# transmitter.net
KiCad netlist of a schematic drawn in EAGLE
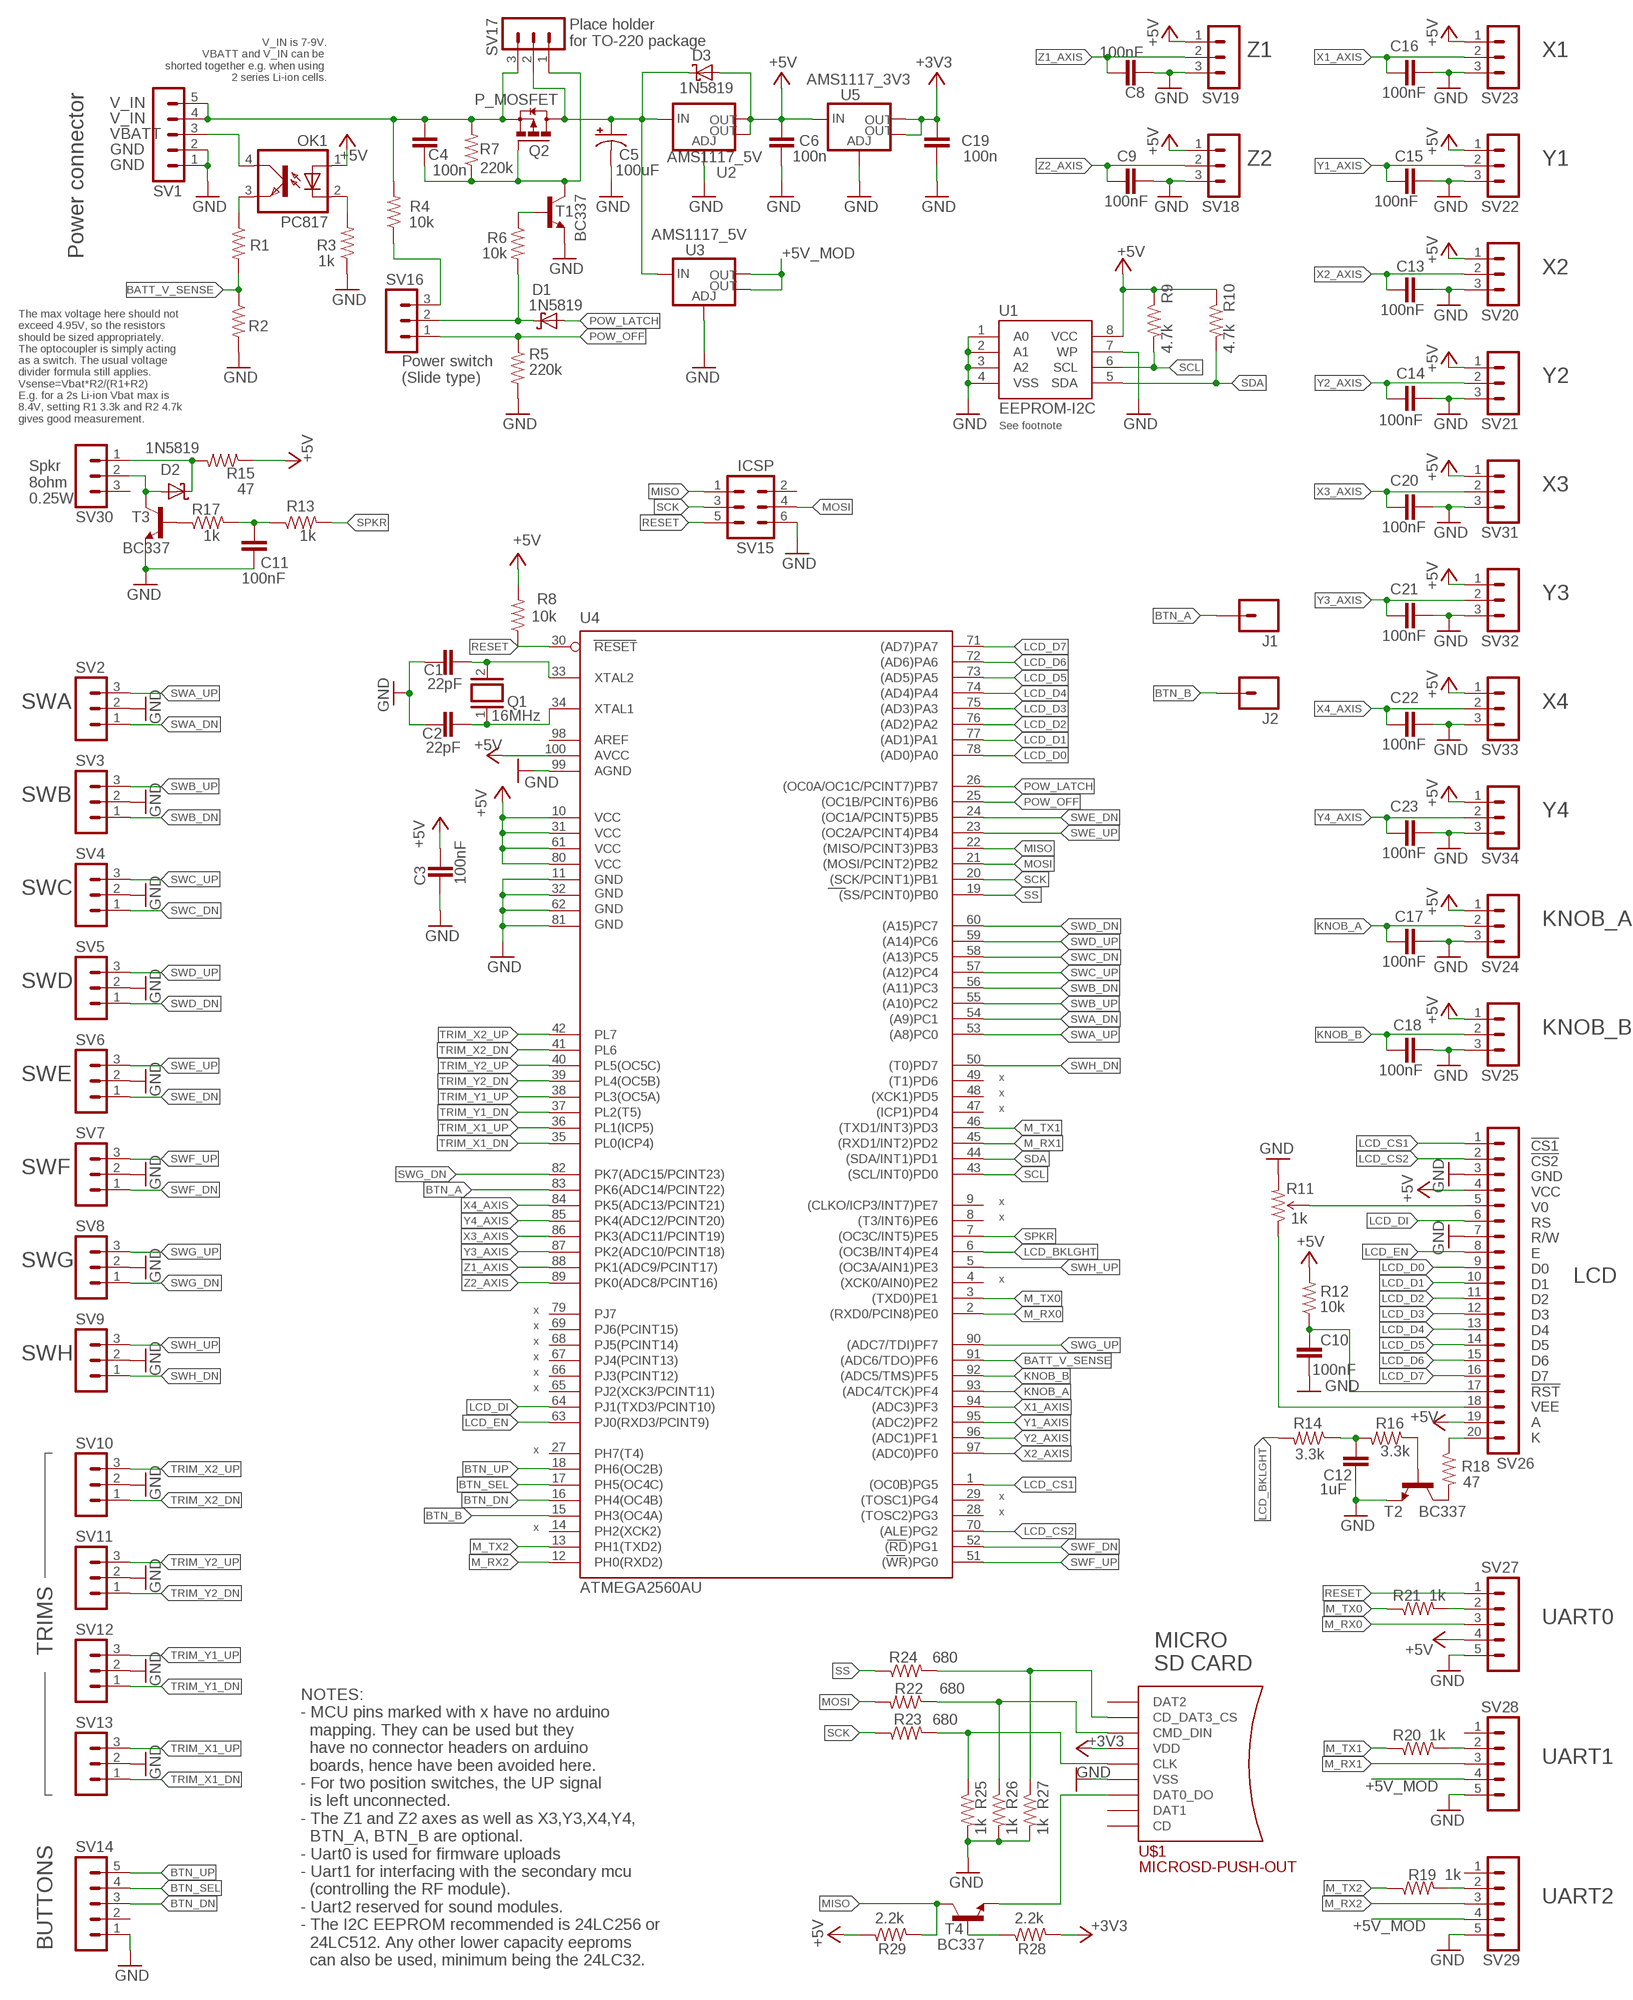
[diagram p0: schematic, sheet 1]

(export (version "E")
  (design (tool "Eeschema 10.0.6"))
  (components
    (comp (ref "C1")
      (value "22pF")
      (footprint "eagle-import:C050-024X044")
      (libsource (lib "eagle-import") (part "C-EU050-024X044"))
    )
    (comp (ref "C2")
      (value "22pF")
      (footprint "eagle-import:C050-024X044")
      (libsource (lib "eagle-import") (part "C-EU050-024X044"))
    )
    (comp (ref "C3")
      (value "100nF")
      (footprint "eagle-import:C050-024X044")
      (libsource (lib "eagle-import") (part "C-EU050-024X044"))
    )
    (comp (ref "C4")
      (value "100n")
      (footprint "eagle-import:C050-024X044")
      (libsource (lib "eagle-import") (part "C-EU050-024X044"))
    )
    (comp (ref "C5")
      (value "100uF")
      (footprint "eagle-import:E2,5-6E")
      (libsource (lib "eagle-import") (part "CPOL-USE2,5-6E"))
    )
    (comp (ref "C6")
      (value "100n")
      (footprint "eagle-import:C050-024X044")
      (libsource (lib "eagle-import") (part "C-EU050-024X044"))
    )
    (comp (ref "C8")
      (value "100nF")
      (footprint "eagle-import:C050-024X044")
      (libsource (lib "eagle-import") (part "C-EU050-024X044"))
    )
    (comp (ref "C9")
      (value "100nF")
      (footprint "eagle-import:C050-024X044")
      (libsource (lib "eagle-import") (part "C-EU050-024X044"))
    )
    (comp (ref "C10")
      (value "100nF")
      (footprint "eagle-import:C050-024X044")
      (libsource (lib "eagle-import") (part "C-EU050-024X044"))
    )
    (comp (ref "C11")
      (value "100nF")
      (footprint "eagle-import:C050-024X044")
      (libsource (lib "eagle-import") (part "C-EU050-024X044"))
    )
    (comp (ref "C12")
      (value "1uF")
      (footprint "eagle-import:C050-024X044")
      (libsource (lib "eagle-import") (part "C-EU050-024X044"))
    )
    (comp (ref "C13")
      (value "100nF")
      (footprint "eagle-import:C050-024X044")
      (libsource (lib "eagle-import") (part "C-EU050-024X044"))
    )
    (comp (ref "C14")
      (value "100nF")
      (footprint "eagle-import:C050-024X044")
      (libsource (lib "eagle-import") (part "C-EU050-024X044"))
    )
    (comp (ref "C15")
      (value "100nF")
      (footprint "eagle-import:C050-024X044")
      (libsource (lib "eagle-import") (part "C-EU050-024X044"))
    )
    (comp (ref "C16")
      (value "100nF")
      (footprint "eagle-import:C050-024X044")
      (libsource (lib "eagle-import") (part "C-EU050-024X044"))
    )
    (comp (ref "C17")
      (value "100nF")
      (footprint "eagle-import:C050-024X044")
      (libsource (lib "eagle-import") (part "C-EU050-024X044"))
    )
    (comp (ref "C18")
      (value "100nF")
      (footprint "eagle-import:C050-024X044")
      (libsource (lib "eagle-import") (part "C-EU050-024X044"))
    )
    (comp (ref "C19")
      (value "100n")
      (footprint "eagle-import:C050-024X044")
      (libsource (lib "eagle-import") (part "C-EU050-024X044"))
    )
    (comp (ref "C20")
      (value "100nF")
      (footprint "eagle-import:C050-024X044")
      (libsource (lib "eagle-import") (part "C-EU050-024X044"))
    )
    (comp (ref "C21")
      (value "100nF")
      (footprint "eagle-import:C050-024X044")
      (libsource (lib "eagle-import") (part "C-EU050-024X044"))
    )
    (comp (ref "C22")
      (value "100nF")
      (footprint "eagle-import:C050-024X044")
      (libsource (lib "eagle-import") (part "C-EU050-024X044"))
    )
    (comp (ref "C23")
      (value "100nF")
      (footprint "eagle-import:C050-024X044")
      (libsource (lib "eagle-import") (part "C-EU050-024X044"))
    )
    (comp (ref "D1")
      (value "1N5819")
      (footprint "eagle-import:DO41-7.6")
      (libsource (lib "eagle-import") (part "1N5817-B"))
    )
    (comp (ref "D2")
      (value "1N5819")
      (footprint "eagle-import:DO41-7.6")
      (libsource (lib "eagle-import") (part "1N5817-B"))
    )
    (comp (ref "D3")
      (value "1N5819")
      (footprint "eagle-import:DO41-7.6")
      (libsource (lib "eagle-import") (part "1N5817-B"))
    )
    (comp (ref "J1")
      (value "M01PTH_LONGPAD")
      (footprint "eagle-import:1X01_LONGPAD")
      (libsource (lib "eagle-import") (part "M01PTH_LONGPAD"))
    )
    (comp (ref "J2")
      (value "M01PTH_LONGPAD")
      (footprint "eagle-import:1X01_LONGPAD")
      (libsource (lib "eagle-import") (part "M01PTH_LONGPAD"))
    )
    (comp (ref "OK1")
      (value "PC817")
      (footprint "eagle-import:DIL04")
      (fields (field (name "MPN") "PC817X4J000F"))
      (libsource (lib "eagle-import") (part "PC817"))
    )
    (comp (ref "Q1")
      (value "16MHz")
      (footprint "eagle-import:QS")
      (libsource (lib "eagle-import") (part "XTAL/S"))
    )
    (comp (ref "Q2")
      (value "P_MOSFET")
      (footprint "eagle-import:SUPER-SOT3")
      (libsource (lib "eagle-import") (part "FDN360P"))
    )
    (comp (ref "R1")
      (value "1k")
      (footprint "eagle-import:0204_5")
      (libsource (lib "eagle-import") (part "R-US_0204/5"))
    )
    (comp (ref "R2")
      (value "1k")
      (footprint "eagle-import:0204_5")
      (libsource (lib "eagle-import") (part "R-US_0204/5"))
    )
    (comp (ref "R3")
      (value "1k")
      (footprint "eagle-import:0204_5")
      (libsource (lib "eagle-import") (part "R-US_0204/5"))
    )
    (comp (ref "R4")
      (value "10k")
      (footprint "eagle-import:0204_5")
      (libsource (lib "eagle-import") (part "R-US_0204/5"))
    )
    (comp (ref "R5")
      (value "220k")
      (footprint "eagle-import:0204_5")
      (libsource (lib "eagle-import") (part "R-US_0204/5"))
    )
    (comp (ref "R6")
      (value "10k")
      (footprint "eagle-import:0204_5")
      (libsource (lib "eagle-import") (part "R-US_0204/5"))
    )
    (comp (ref "R7")
      (value "220k")
      (footprint "eagle-import:0204_5")
      (libsource (lib "eagle-import") (part "R-US_0204/5"))
    )
    (comp (ref "R8")
      (value "10k")
      (footprint "eagle-import:0204_5")
      (libsource (lib "eagle-import") (part "R-US_0204/5"))
    )
    (comp (ref "R9")
      (value "4.7k")
      (footprint "eagle-import:0204_5")
      (libsource (lib "eagle-import") (part "R-US_0204/5"))
    )
    (comp (ref "R10")
      (value "4.7k")
      (footprint "eagle-import:0204_5")
      (libsource (lib "eagle-import") (part "R-US_0204/5"))
    )
    (comp (ref "R11")
      (value "1k")
      (footprint "eagle-import:TRIM_POT_PTH")
      (libsource (lib "eagle-import") (part "TRIMPOTPTH"))
    )
    (comp (ref "R12")
      (value "10k")
      (footprint "eagle-import:0204_5")
      (libsource (lib "eagle-import") (part "resistor_R-US_0204/5"))
    )
    (comp (ref "R13")
      (value "1k")
      (footprint "eagle-import:0204_5")
      (libsource (lib "eagle-import") (part "R-US_0204/5"))
    )
    (comp (ref "R14")
      (value "3.3k")
      (footprint "eagle-import:0204_5")
      (libsource (lib "eagle-import") (part "R-US_0204/5"))
    )
    (comp (ref "R15")
      (value "47")
      (footprint "eagle-import:0204_5")
      (libsource (lib "eagle-import") (part "R-US_0204/5"))
    )
    (comp (ref "R16")
      (value "3.3k")
      (footprint "eagle-import:0204_5")
      (libsource (lib "eagle-import") (part "R-US_0204/5"))
    )
    (comp (ref "R17")
      (value "1k")
      (footprint "eagle-import:0204_5")
      (libsource (lib "eagle-import") (part "R-US_0204/5"))
    )
    (comp (ref "R18")
      (value "47")
      (footprint "eagle-import:0204_5")
      (libsource (lib "eagle-import") (part "R-US_0204/5"))
    )
    (comp (ref "R19")
      (value "1k")
      (footprint "eagle-import:0204_5")
      (libsource (lib "eagle-import") (part "R-US_0204/5"))
    )
    (comp (ref "R20")
      (value "1k")
      (footprint "eagle-import:0204_5")
      (libsource (lib "eagle-import") (part "R-US_0204/5"))
    )
    (comp (ref "R21")
      (value "1k")
      (footprint "eagle-import:0204_5")
      (libsource (lib "eagle-import") (part "R-US_0204/5"))
    )
    (comp (ref "R22")
      (value "680")
      (footprint "eagle-import:0204_5")
      (libsource (lib "eagle-import") (part "R-US_0204/5"))
    )
    (comp (ref "R23")
      (value "680")
      (footprint "eagle-import:0204_5")
      (libsource (lib "eagle-import") (part "R-US_0204/5"))
    )
    (comp (ref "R24")
      (value "680")
      (footprint "eagle-import:0204_5")
      (libsource (lib "eagle-import") (part "R-US_0204/5"))
    )
    (comp (ref "R25")
      (value "1k")
      (footprint "eagle-import:0204_5")
      (libsource (lib "eagle-import") (part "R-US_0204/5"))
    )
    (comp (ref "R26")
      (value "1k")
      (footprint "eagle-import:0204_5")
      (libsource (lib "eagle-import") (part "R-US_0204/5"))
    )
    (comp (ref "R27")
      (value "1k")
      (footprint "eagle-import:0204_5")
      (libsource (lib "eagle-import") (part "R-US_0204/5"))
    )
    (comp (ref "R28")
      (value "2.2k")
      (footprint "eagle-import:0204_5")
      (libsource (lib "eagle-import") (part "R-US_0204/5"))
    )
    (comp (ref "R29")
      (value "2.2k")
      (footprint "eagle-import:0204_5")
      (libsource (lib "eagle-import") (part "R-US_0204/5"))
    )
    (comp (ref "SV1")
      (value "MA05-1")
      (footprint "eagle-import:MA05-1")
      (libsource (lib "eagle-import") (part "MA05-1"))
    )
    (comp (ref "SV2")
      (value "MA03-1")
      (footprint "eagle-import:MA03-1")
      (libsource (lib "eagle-import") (part "MA03-1"))
    )
    (comp (ref "SV3")
      (value "MA03-1")
      (footprint "eagle-import:MA03-1")
      (libsource (lib "eagle-import") (part "MA03-1"))
    )
    (comp (ref "SV4")
      (value "MA03-1")
      (footprint "eagle-import:MA03-1")
      (libsource (lib "eagle-import") (part "MA03-1"))
    )
    (comp (ref "SV5")
      (value "MA03-1")
      (footprint "eagle-import:MA03-1")
      (libsource (lib "eagle-import") (part "MA03-1"))
    )
    (comp (ref "SV6")
      (value "MA03-1")
      (footprint "eagle-import:MA03-1")
      (libsource (lib "eagle-import") (part "MA03-1"))
    )
    (comp (ref "SV7")
      (value "MA03-1")
      (footprint "eagle-import:MA03-1")
      (libsource (lib "eagle-import") (part "MA03-1"))
    )
    (comp (ref "SV8")
      (value "MA03-1")
      (footprint "eagle-import:MA03-1")
      (libsource (lib "eagle-import") (part "MA03-1"))
    )
    (comp (ref "SV9")
      (value "MA03-1")
      (footprint "eagle-import:MA03-1")
      (libsource (lib "eagle-import") (part "MA03-1"))
    )
    (comp (ref "SV10")
      (value "MA03-1")
      (footprint "eagle-import:MA03-1")
      (libsource (lib "eagle-import") (part "MA03-1"))
    )
    (comp (ref "SV11")
      (value "MA03-1")
      (footprint "eagle-import:MA03-1")
      (libsource (lib "eagle-import") (part "MA03-1"))
    )
    (comp (ref "SV12")
      (value "MA03-1")
      (footprint "eagle-import:MA03-1")
      (libsource (lib "eagle-import") (part "MA03-1"))
    )
    (comp (ref "SV13")
      (value "MA03-1")
      (footprint "eagle-import:MA03-1")
      (libsource (lib "eagle-import") (part "MA03-1"))
    )
    (comp (ref "SV14")
      (value "MA05-1")
      (footprint "eagle-import:MA05-1")
      (libsource (lib "eagle-import") (part "MA05-1"))
    )
    (comp (ref "SV15")
      (value "ICSP")
      (footprint "eagle-import:MA03-2")
      (libsource (lib "eagle-import") (part "MA03-2"))
    )
    (comp (ref "SV16")
      (value "MA03-1")
      (footprint "eagle-import:MA03-1")
      (libsource (lib "eagle-import") (part "MA03-1"))
    )
    (comp (ref "SV17")
      (value "MA03-1")
      (footprint "eagle-import:MA03-1")
      (libsource (lib "eagle-import") (part "MA03-1"))
    )
    (comp (ref "SV18")
      (value "MA03-1")
      (footprint "eagle-import:MA03-1")
      (libsource (lib "eagle-import") (part "MA03-1"))
    )
    (comp (ref "SV19")
      (value "MA03-1")
      (footprint "eagle-import:MA03-1")
      (libsource (lib "eagle-import") (part "MA03-1"))
    )
    (comp (ref "SV20")
      (value "MA03-1")
      (footprint "eagle-import:MA03-1")
      (libsource (lib "eagle-import") (part "MA03-1"))
    )
    (comp (ref "SV21")
      (value "MA03-1")
      (footprint "eagle-import:MA03-1")
      (libsource (lib "eagle-import") (part "MA03-1"))
    )
    (comp (ref "SV22")
      (value "MA03-1")
      (footprint "eagle-import:MA03-1")
      (libsource (lib "eagle-import") (part "MA03-1"))
    )
    (comp (ref "SV23")
      (value "MA03-1")
      (footprint "eagle-import:MA03-1")
      (libsource (lib "eagle-import") (part "MA03-1"))
    )
    (comp (ref "SV24")
      (value "MA03-1")
      (footprint "eagle-import:MA03-1")
      (libsource (lib "eagle-import") (part "MA03-1"))
    )
    (comp (ref "SV25")
      (value "MA03-1")
      (footprint "eagle-import:MA03-1")
      (libsource (lib "eagle-import") (part "MA03-1"))
    )
    (comp (ref "SV26")
      (value "MA20-1")
      (footprint "eagle-import:MA20-1")
      (libsource (lib "eagle-import") (part "MA20-1"))
    )
    (comp (ref "SV27")
      (value "MA05-1")
      (footprint "eagle-import:MA05-1")
      (libsource (lib "eagle-import") (part "MA05-1"))
    )
    (comp (ref "SV28")
      (value "MA05-1")
      (footprint "eagle-import:MA05-1")
      (libsource (lib "eagle-import") (part "MA05-1"))
    )
    (comp (ref "SV29")
      (value "MA05-1")
      (footprint "eagle-import:MA05-1")
      (libsource (lib "eagle-import") (part "MA05-1"))
    )
    (comp (ref "SV30")
      (value "MA03-1")
      (footprint "eagle-import:MA03-1")
      (libsource (lib "eagle-import") (part "MA03-1"))
    )
    (comp (ref "SV31")
      (value "MA03-1")
      (footprint "eagle-import:MA03-1")
      (libsource (lib "eagle-import") (part "MA03-1"))
    )
    (comp (ref "SV32")
      (value "MA03-1")
      (footprint "eagle-import:MA03-1")
      (libsource (lib "eagle-import") (part "MA03-1"))
    )
    (comp (ref "SV33")
      (value "MA03-1")
      (footprint "eagle-import:MA03-1")
      (libsource (lib "eagle-import") (part "MA03-1"))
    )
    (comp (ref "SV34")
      (value "MA03-1")
      (footprint "eagle-import:MA03-1")
      (libsource (lib "eagle-import") (part "MA03-1"))
    )
    (comp (ref "T1")
      (value "BC337")
      (footprint "eagle-import:TO92")
      (libsource (lib "eagle-import") (part "BC337"))
    )
    (comp (ref "T2")
      (value "BC337")
      (footprint "eagle-import:TO92")
      (libsource (lib "eagle-import") (part "BC337"))
    )
    (comp (ref "T3")
      (value "BC337")
      (footprint "eagle-import:TO92")
      (libsource (lib "eagle-import") (part "BC337"))
    )
    (comp (ref "T4")
      (value "BC337")
      (footprint "eagle-import:TO92")
      (libsource (lib "eagle-import") (part "BC337"))
    )
    (comp (ref "U$1")
      (value "MICROSD-PUSH-OUT")
      (footprint "eagle-import:MICROSD-PUSH-OUT")
      (libsource (lib "eagle-import") (part "MICROSD-PUSH-OUT"))
    )
    (comp (ref "U1")
      (value "EEPROM-I2C")
      (footprint "eagle-import:SO08-EIAJ")
      (libsource (lib "eagle-import") (part "EEPROM-I2CEIAJ"))
    )
    (comp (ref "U2")
      (value "AMS1117_5V")
      (footprint "eagle-import:SOT223")
      (libsource (lib "eagle-import") (part "V_REG_LM1117SOT223"))
    )
    (comp (ref "U3")
      (value "AMS1117_5V")
      (footprint "eagle-import:SOT223")
      (libsource (lib "eagle-import") (part "V_REG_LM1117SOT223"))
    )
    (comp (ref "U4")
      (value "ATMEGA2560AU")
      (footprint "eagle-import:TQFP100")
      (libsource (lib "eagle-import") (part "ATMEGA2560AU"))
    )
    (comp (ref "U5")
      (value "AMS1117_3V3")
      (footprint "eagle-import:SOT223")
      (libsource (lib "eagle-import") (part "V_REG_LM1117SOT223"))
    )
  )
  (nets
    (net (code "1") (name "+3V3") (class "Default")
      (node (ref "C19") (pin "2") (pinfunction "2_2") (pintype "passive"))
      (node (ref "R28") (pin "2") (pinfunction "2_2") (pintype "passive"))
      (node (ref "U$1") (pin "4") (pinfunction "VDD_4") (pintype "bidirectional"))
      (node (ref "U5") (pin "2") (pinfunction "OUT_2") (pintype "output"))
      (node (ref "U5") (pin "4") (pinfunction "OUT_4") (pintype "output"))
    )
    (net (code "2") (name "+5V") (class "Default")
      (node (ref "C3") (pin "1") (pinfunction "1_1") (pintype "passive"))
      (node (ref "C6") (pin "2") (pinfunction "2_2") (pintype "passive"))
      (node (ref "D3") (pin "A") (pinfunction "A_A") (pintype "passive"))
      (node (ref "OK1") (pin "1") (pinfunction "A_1") (pintype "passive"))
      (node (ref "R10") (pin "1") (pinfunction "1_1") (pintype "passive"))
      (node (ref "R12") (pin "2") (pinfunction "2_2") (pintype "passive"))
      (node (ref "R15") (pin "1") (pinfunction "1_1") (pintype "passive"))
      (node (ref "R29") (pin "1") (pinfunction "1_1") (pintype "passive"))
      (node (ref "R8") (pin "2") (pinfunction "2_2") (pintype "passive"))
      (node (ref "R9") (pin "1") (pinfunction "1_1") (pintype "passive"))
      (node (ref "SV18") (pin "1") (pinfunction "1_1") (pintype "passive"))
      (node (ref "SV19") (pin "1") (pinfunction "1_1") (pintype "passive"))
      (node (ref "SV20") (pin "1") (pinfunction "1_1") (pintype "passive"))
      (node (ref "SV21") (pin "1") (pinfunction "1_1") (pintype "passive"))
      (node (ref "SV22") (pin "1") (pinfunction "1_1") (pintype "passive"))
      (node (ref "SV23") (pin "1") (pinfunction "1_1") (pintype "passive"))
      (node (ref "SV24") (pin "1") (pinfunction "1_1") (pintype "passive"))
      (node (ref "SV25") (pin "1") (pinfunction "1_1") (pintype "passive"))
      (node (ref "SV26") (pin "19") (pinfunction "19_19") (pintype "passive"))
      (node (ref "SV26") (pin "4") (pinfunction "4_4") (pintype "passive"))
      (node (ref "SV27") (pin "4") (pinfunction "4_4") (pintype "passive"))
      (node (ref "SV31") (pin "1") (pinfunction "1_1") (pintype "passive"))
      (node (ref "SV32") (pin "1") (pinfunction "1_1") (pintype "passive"))
      (node (ref "SV33") (pin "1") (pinfunction "1_1") (pintype "passive"))
      (node (ref "SV34") (pin "1") (pinfunction "1_1") (pintype "passive"))
      (node (ref "U1") (pin "8") (pinfunction "VCC_8") (pintype "power_in"))
      (node (ref "U2") (pin "2") (pinfunction "OUT_2") (pintype "output"))
      (node (ref "U2") (pin "4") (pinfunction "OUT_4") (pintype "output"))
      (node (ref "U4") (pin "10") (pinfunction "VCC_10") (pintype "power_in"))
      (node (ref "U4") (pin "100") (pinfunction "AVCC_100") (pintype "power_in"))
      (node (ref "U4") (pin "31") (pinfunction "VCC1_31") (pintype "power_in"))
      (node (ref "U4") (pin "61") (pinfunction "VCC2_61") (pintype "power_in"))
      (node (ref "U4") (pin "80") (pinfunction "VCC3_80") (pintype "power_in"))
      (node (ref "U5") (pin "3") (pinfunction "IN_3") (pintype "input"))
    )
    (net (code "3") (name "/+5V_MOD") (class "Default")
      (node (ref "SV28") (pin "4") (pinfunction "4_4") (pintype "passive"))
      (node (ref "SV29") (pin "4") (pinfunction "4_4") (pintype "passive"))
      (node (ref "U3") (pin "2") (pinfunction "OUT_2") (pintype "output"))
      (node (ref "U3") (pin "4") (pinfunction "OUT_4") (pintype "output"))
    )
    (net (code "4") (name "BATT_V_SENSE") (class "Default")
      (node (ref "R1") (pin "2") (pinfunction "2_2") (pintype "passive"))
      (node (ref "R2") (pin "1") (pinfunction "1_1") (pintype "passive"))
      (node (ref "U4") (pin "91") (pinfunction "(ADC6/TDO)PF6_91") (pintype "bidirectional"))
    )
    (net (code "5") (name "BTN_A") (class "Default")
      (node (ref "J1") (pin "1") (pinfunction "1_1") (pintype "passive"))
      (node (ref "U4") (pin "83") (pinfunction "PK6(ADC14/PCINT22)_83") (pintype "bidirectional"))
    )
    (net (code "6") (name "BTN_B") (class "Default")
      (node (ref "J2") (pin "1") (pinfunction "1_1") (pintype "passive"))
      (node (ref "U4") (pin "15") (pinfunction "PH3(OC4A)_15") (pintype "bidirectional"))
    )
    (net (code "7") (name "BTN_DN") (class "Default")
      (node (ref "SV14") (pin "3") (pinfunction "3_3") (pintype "passive"))
      (node (ref "U4") (pin "16") (pinfunction "PH4(OC4B)_16") (pintype "bidirectional"))
    )
    (net (code "8") (name "BTN_SEL") (class "Default")
      (node (ref "SV14") (pin "4") (pinfunction "4_4") (pintype "passive"))
      (node (ref "U4") (pin "17") (pinfunction "PH5(OC4C)_17") (pintype "bidirectional"))
    )
    (net (code "9") (name "BTN_UP") (class "Default")
      (node (ref "SV14") (pin "5") (pinfunction "5_5") (pintype "passive"))
      (node (ref "U4") (pin "18") (pinfunction "PH6(OC2B)_18") (pintype "bidirectional"))
    )
    (net (code "10") (name "GND") (class "Default")
      (node (ref "C1") (pin "1") (pinfunction "1_1") (pintype "passive"))
      (node (ref "C10") (pin "2") (pinfunction "2_2") (pintype "passive"))
      (node (ref "C11") (pin "2") (pinfunction "2_2") (pintype "passive"))
      (node (ref "C12") (pin "2") (pinfunction "2_2") (pintype "passive"))
      (node (ref "C13") (pin "1") (pinfunction "1_1") (pintype "passive"))
      (node (ref "C14") (pin "1") (pinfunction "1_1") (pintype "passive"))
      (node (ref "C15") (pin "1") (pinfunction "1_1") (pintype "passive"))
      (node (ref "C16") (pin "1") (pinfunction "1_1") (pintype "passive"))
      (node (ref "C17") (pin "1") (pinfunction "1_1") (pintype "passive"))
      (node (ref "C18") (pin "1") (pinfunction "1_1") (pintype "passive"))
      (node (ref "C19") (pin "1") (pinfunction "1_1") (pintype "passive"))
      (node (ref "C2") (pin "1") (pinfunction "1_1") (pintype "passive"))
      (node (ref "C20") (pin "1") (pinfunction "1_1") (pintype "passive"))
      (node (ref "C21") (pin "1") (pinfunction "1_1") (pintype "passive"))
      (node (ref "C22") (pin "1") (pinfunction "1_1") (pintype "passive"))
      (node (ref "C23") (pin "1") (pinfunction "1_1") (pintype "passive"))
      (node (ref "C3") (pin "2") (pinfunction "2_2") (pintype "passive"))
      (node (ref "C5") (pin "-") (pinfunction "-_-") (pintype "passive"))
      (node (ref "C6") (pin "1") (pinfunction "1_1") (pintype "passive"))
      (node (ref "C8") (pin "2") (pinfunction "2_2") (pintype "passive"))
      (node (ref "C9") (pin "1") (pinfunction "1_1") (pintype "passive"))
      (node (ref "R11") (pin "3") (pinfunction "CW_3") (pintype "passive"))
      (node (ref "R2") (pin "2") (pinfunction "2_2") (pintype "passive"))
      (node (ref "R25") (pin "2") (pinfunction "2_2") (pintype "passive"))
      (node (ref "R26") (pin "2") (pinfunction "2_2") (pintype "passive"))
      (node (ref "R27") (pin "2") (pinfunction "2_2") (pintype "passive"))
      (node (ref "R3") (pin "1") (pinfunction "1_1") (pintype "passive"))
      (node (ref "R5") (pin "2") (pinfunction "2_2") (pintype "passive"))
      (node (ref "SV1") (pin "1") (pinfunction "1_1") (pintype "passive"))
      (node (ref "SV1") (pin "2") (pinfunction "2_2") (pintype "passive"))
      (node (ref "SV10") (pin "2") (pinfunction "2_2") (pintype "passive"))
      (node (ref "SV11") (pin "2") (pinfunction "2_2") (pintype "passive"))
      (node (ref "SV12") (pin "2") (pinfunction "2_2") (pintype "passive"))
      (node (ref "SV13") (pin "2") (pinfunction "2_2") (pintype "passive"))
      (node (ref "SV14") (pin "1") (pinfunction "1_1") (pintype "passive"))
      (node (ref "SV15") (pin "6") (pinfunction "6_6") (pintype "passive"))
      (node (ref "SV18") (pin "3") (pinfunction "3_3") (pintype "passive"))
      (node (ref "SV19") (pin "3") (pinfunction "3_3") (pintype "passive"))
      (node (ref "SV2") (pin "2") (pinfunction "2_2") (pintype "passive"))
      (node (ref "SV20") (pin "3") (pinfunction "3_3") (pintype "passive"))
      (node (ref "SV21") (pin "3") (pinfunction "3_3") (pintype "passive"))
      (node (ref "SV22") (pin "3") (pinfunction "3_3") (pintype "passive"))
      (node (ref "SV23") (pin "3") (pinfunction "3_3") (pintype "passive"))
      (node (ref "SV24") (pin "3") (pinfunction "3_3") (pintype "passive"))
      (node (ref "SV25") (pin "3") (pinfunction "3_3") (pintype "passive"))
      (node (ref "SV26") (pin "3") (pinfunction "3_3") (pintype "passive"))
      (node (ref "SV26") (pin "7") (pinfunction "7_7") (pintype "passive"))
      (node (ref "SV27") (pin "5") (pinfunction "5_5") (pintype "passive"))
      (node (ref "SV28") (pin "5") (pinfunction "5_5") (pintype "passive"))
      (node (ref "SV29") (pin "5") (pinfunction "5_5") (pintype "passive"))
      (node (ref "SV3") (pin "2") (pinfunction "2_2") (pintype "passive"))
      (node (ref "SV31") (pin "3") (pinfunction "3_3") (pintype "passive"))
      (node (ref "SV32") (pin "3") (pinfunction "3_3") (pintype "passive"))
      (node (ref "SV33") (pin "3") (pinfunction "3_3") (pintype "passive"))
      (node (ref "SV34") (pin "3") (pinfunction "3_3") (pintype "passive"))
      (node (ref "SV4") (pin "2") (pinfunction "2_2") (pintype "passive"))
      (node (ref "SV5") (pin "2") (pinfunction "2_2") (pintype "passive"))
      (node (ref "SV6") (pin "2") (pinfunction "2_2") (pintype "passive"))
      (node (ref "SV7") (pin "2") (pinfunction "2_2") (pintype "passive"))
      (node (ref "SV8") (pin "2") (pinfunction "2_2") (pintype "passive"))
      (node (ref "SV9") (pin "2") (pinfunction "2_2") (pintype "passive"))
      (node (ref "T1") (pin "1") (pinfunction "E_1") (pintype "passive"))
      (node (ref "T2") (pin "1") (pinfunction "E_1") (pintype "passive"))
      (node (ref "T3") (pin "1") (pinfunction "E_1") (pintype "passive"))
      (node (ref "U$1") (pin "6") (pinfunction "VSS_6") (pintype "bidirectional"))
      (node (ref "U$1") (pin "G1") (pinfunction "VSS_G1") (pintype "bidirectional"))
      (node (ref "U$1") (pin "G2") (pinfunction "VSS_G2") (pintype "bidirectional"))
      (node (ref "U$1") (pin "G3") (pinfunction "VSS_G3") (pintype "bidirectional"))
      (node (ref "U$1") (pin "G4") (pinfunction "VSS_G4") (pintype "bidirectional"))
      (node (ref "U1") (pin "1") (pinfunction "A0_1") (pintype "bidirectional"))
      (node (ref "U1") (pin "2") (pinfunction "A1_2") (pintype "bidirectional"))
      (node (ref "U1") (pin "3") (pinfunction "A2_3") (pintype "bidirectional"))
      (node (ref "U1") (pin "4") (pinfunction "VSS_4") (pintype "power_in"))
      (node (ref "U1") (pin "7") (pinfunction "WP_7") (pintype "bidirectional"))
      (node (ref "U2") (pin "1") (pinfunction "ADJ_1") (pintype "input"))
      (node (ref "U3") (pin "1") (pinfunction "ADJ_1") (pintype "input"))
      (node (ref "U4") (pin "11") (pinfunction "GND_11") (pintype "power_in"))
      (node (ref "U4") (pin "32") (pinfunction "GND1_32") (pintype "power_in"))
      (node (ref "U4") (pin "62") (pinfunction "GND2_62") (pintype "power_in"))
      (node (ref "U4") (pin "81") (pinfunction "GND3_81") (pintype "power_in"))
      (node (ref "U4") (pin "99") (pinfunction "AGND_99") (pintype "power_in"))
      (node (ref "U5") (pin "1") (pinfunction "ADJ_1") (pintype "input"))
    )
    (net (code "11") (name "KNOB_A") (class "Default")
      (node (ref "C17") (pin "2") (pinfunction "2_2") (pintype "passive"))
      (node (ref "SV24") (pin "2") (pinfunction "2_2") (pintype "passive"))
      (node (ref "U4") (pin "93") (pinfunction "(ADC4/TCK)PF4_93") (pintype "bidirectional"))
    )
    (net (code "12") (name "KNOB_B") (class "Default")
      (node (ref "C18") (pin "2") (pinfunction "2_2") (pintype "passive"))
      (node (ref "SV25") (pin "2") (pinfunction "2_2") (pintype "passive"))
      (node (ref "U4") (pin "92") (pinfunction "(ADC5/TMS)PF5_92") (pintype "bidirectional"))
    )
    (net (code "13") (name "LCD_BKLGHT") (class "Default")
      (node (ref "R14") (pin "2") (pinfunction "2_2") (pintype "passive"))
      (node (ref "U4") (pin "6") (pinfunction "(OC3B/INT4)PE4_6") (pintype "bidirectional"))
    )
    (net (code "14") (name "LCD_CS1") (class "Default")
      (node (ref "SV26") (pin "1") (pinfunction "1_1") (pintype "passive"))
      (node (ref "U4") (pin "1") (pinfunction "(OC0B)PG5_1") (pintype "bidirectional"))
    )
    (net (code "15") (name "LCD_CS2") (class "Default")
      (node (ref "SV26") (pin "2") (pinfunction "2_2") (pintype "passive"))
      (node (ref "U4") (pin "70") (pinfunction "(ALE)PG2_70") (pintype "bidirectional"))
    )
    (net (code "16") (name "LCD_D0") (class "Default")
      (node (ref "SV26") (pin "9") (pinfunction "9_9") (pintype "passive"))
      (node (ref "U4") (pin "78") (pinfunction "(AD0)PA0_78") (pintype "bidirectional"))
    )
    (net (code "17") (name "LCD_D1") (class "Default")
      (node (ref "SV26") (pin "10") (pinfunction "10_10") (pintype "passive"))
      (node (ref "U4") (pin "77") (pinfunction "(AD1)PA1_77") (pintype "bidirectional"))
    )
    (net (code "18") (name "LCD_D2") (class "Default")
      (node (ref "SV26") (pin "11") (pinfunction "11_11") (pintype "passive"))
      (node (ref "U4") (pin "76") (pinfunction "(AD2)PA2_76") (pintype "bidirectional"))
    )
    (net (code "19") (name "LCD_D3") (class "Default")
      (node (ref "SV26") (pin "12") (pinfunction "12_12") (pintype "passive"))
      (node (ref "U4") (pin "75") (pinfunction "(AD3)PA3_75") (pintype "bidirectional"))
    )
    (net (code "20") (name "LCD_D4") (class "Default")
      (node (ref "SV26") (pin "13") (pinfunction "13_13") (pintype "passive"))
      (node (ref "U4") (pin "74") (pinfunction "(AD4)PA4_74") (pintype "bidirectional"))
    )
    (net (code "21") (name "LCD_D5") (class "Default")
      (node (ref "SV26") (pin "14") (pinfunction "14_14") (pintype "passive"))
      (node (ref "U4") (pin "73") (pinfunction "(AD5)PA5_73") (pintype "bidirectional"))
    )
    (net (code "22") (name "LCD_D6") (class "Default")
      (node (ref "SV26") (pin "15") (pinfunction "15_15") (pintype "passive"))
      (node (ref "U4") (pin "72") (pinfunction "(AD6)PA6_72") (pintype "bidirectional"))
    )
    (net (code "23") (name "LCD_D7") (class "Default")
      (node (ref "SV26") (pin "16") (pinfunction "16_16") (pintype "passive"))
      (node (ref "U4") (pin "71") (pinfunction "(AD7)PA7_71") (pintype "bidirectional"))
    )
    (net (code "24") (name "LCD_DI") (class "Default")
      (node (ref "SV26") (pin "6") (pinfunction "6_6") (pintype "passive"))
      (node (ref "U4") (pin "64") (pinfunction "PJ1(TXD3/PCINT10)_64") (pintype "bidirectional"))
    )
    (net (code "25") (name "LCD_EN") (class "Default")
      (node (ref "SV26") (pin "8") (pinfunction "8_8") (pintype "passive"))
      (node (ref "U4") (pin "63") (pinfunction "PJ0(RXD3/PCINT9)_63") (pintype "bidirectional"))
    )
    (net (code "26") (name "MISO") (class "Default")
      (node (ref "R29") (pin "2") (pinfunction "2_2") (pintype "passive"))
      (node (ref "SV15") (pin "1") (pinfunction "1_1") (pintype "passive"))
      (node (ref "T4") (pin "3") (pinfunction "C_3") (pintype "passive"))
      (node (ref "U4") (pin "22") (pinfunction "(MISO/PCINT3)PB3_22") (pintype "bidirectional"))
    )
    (net (code "27") (name "MOSI") (class "Default")
      (node (ref "R22") (pin "2") (pinfunction "2_2") (pintype "passive"))
      (node (ref "SV15") (pin "4") (pinfunction "4_4") (pintype "passive"))
      (node (ref "U4") (pin "21") (pinfunction "(MOSI/PCINT2)PB2_21") (pintype "bidirectional"))
    )
    (net (code "28") (name "M_RX0") (class "Default")
      (node (ref "SV27") (pin "3") (pinfunction "3_3") (pintype "passive"))
      (node (ref "U4") (pin "2") (pinfunction "(RXD0/PCIN8)PE0_2") (pintype "bidirectional"))
    )
    (net (code "29") (name "M_RX1") (class "Default")
      (node (ref "SV28") (pin "3") (pinfunction "3_3") (pintype "passive"))
      (node (ref "U4") (pin "45") (pinfunction "(RXD1/INT2)PD2_45") (pintype "bidirectional"))
    )
    (net (code "30") (name "M_RX2") (class "Default")
      (node (ref "SV29") (pin "3") (pinfunction "3_3") (pintype "passive"))
      (node (ref "U4") (pin "12") (pinfunction "PH0(RXD2)_12") (pintype "bidirectional"))
    )
    (net (code "31") (name "M_TX0") (class "Default")
      (node (ref "R21") (pin "1") (pinfunction "1_1") (pintype "passive"))
      (node (ref "U4") (pin "3") (pinfunction "(TXD0)PE1_3") (pintype "bidirectional"))
    )
    (net (code "32") (name "M_TX1") (class "Default")
      (node (ref "R20") (pin "1") (pinfunction "1_1") (pintype "passive"))
      (node (ref "U4") (pin "46") (pinfunction "(TXD1/INT3)PD3_46") (pintype "bidirectional"))
    )
    (net (code "33") (name "M_TX2") (class "Default")
      (node (ref "R19") (pin "1") (pinfunction "1_1") (pintype "passive"))
      (node (ref "U4") (pin "13") (pinfunction "PH1(TXD2)_13") (pintype "bidirectional"))
    )
    (net (code "34") (name "Net-(C10-Pad1)") (class "Default")
      (node (ref "C10") (pin "1") (pinfunction "1_1") (pintype "passive"))
      (node (ref "R12") (pin "1") (pinfunction "1_1") (pintype "passive"))
      (node (ref "SV26") (pin "17") (pinfunction "17_17") (pintype "passive"))
    )
    (net (code "35") (name "Net-(C11-Pad1)") (class "Default")
      (node (ref "C11") (pin "1") (pinfunction "1_1") (pintype "passive"))
      (node (ref "R13") (pin "1") (pinfunction "1_1") (pintype "passive"))
      (node (ref "R17") (pin "2") (pinfunction "2_2") (pintype "passive"))
    )
    (net (code "36") (name "Net-(C12-Pad1)") (class "Default")
      (node (ref "C12") (pin "1") (pinfunction "1_1") (pintype "passive"))
      (node (ref "R14") (pin "1") (pinfunction "1_1") (pintype "passive"))
      (node (ref "R16") (pin "2") (pinfunction "2_2") (pintype "passive"))
    )
    (net (code "37") (name "Net-(D1-PadC)") (class "Default")
      (node (ref "D1") (pin "C") (pinfunction "C_C") (pintype "passive"))
      (node (ref "R6") (pin "2") (pinfunction "2_2") (pintype "passive"))
      (node (ref "SV16") (pin "2") (pinfunction "2_2") (pintype "passive"))
    )
    (net (code "38") (name "Net-(D2-PadC)") (class "Default")
      (node (ref "D2") (pin "C") (pinfunction "C_C") (pintype "passive"))
      (node (ref "R15") (pin "2") (pinfunction "2_2") (pintype "passive"))
      (node (ref "SV30") (pin "1") (pinfunction "1_1") (pintype "passive"))
    )
    (net (code "39") (name "Net-(OK1-C)") (class "Default")
      (node (ref "OK1") (pin "2") (pinfunction "C_2") (pintype "passive"))
      (node (ref "R3") (pin "2") (pinfunction "2_2") (pintype "passive"))
    )
    (net (code "40") (name "Net-(OK1-COL)") (class "Default")
      (node (ref "OK1") (pin "4") (pinfunction "COL_4") (pintype "passive"))
      (node (ref "SV1") (pin "3") (pinfunction "3_3") (pintype "passive"))
    )
    (net (code "41") (name "Net-(OK1-EMIT)") (class "Default")
      (node (ref "OK1") (pin "3") (pinfunction "EMIT_3") (pintype "passive"))
      (node (ref "R1") (pin "1") (pinfunction "1_1") (pintype "passive"))
    )
    (net (code "42") (name "Net-(Q2-D)") (class "Default")
      (node (ref "C5") (pin "+") (pinfunction "+_+") (pintype "passive"))
      (node (ref "D3") (pin "C") (pinfunction "C_C") (pintype "passive"))
      (node (ref "Q2") (pin "3") (pinfunction "D_3") (pintype "passive"))
      (node (ref "SV17") (pin "2") (pinfunction "2_2") (pintype "passive"))
      (node (ref "U2") (pin "3") (pinfunction "IN_3") (pintype "input"))
      (node (ref "U3") (pin "3") (pinfunction "IN_3") (pintype "input"))
    )
    (net (code "43") (name "Net-(Q2-G)") (class "Default")
      (node (ref "C4") (pin "1") (pinfunction "1_1") (pintype "passive"))
      (node (ref "Q2") (pin "1") (pinfunction "G_1") (pintype "passive"))
      (node (ref "R7") (pin "1") (pinfunction "1_1") (pintype "passive"))
      (node (ref "SV17") (pin "1") (pinfunction "1_1") (pintype "passive"))
      (node (ref "T1") (pin "3") (pinfunction "C_3") (pintype "passive"))
    )
    (net (code "44") (name "Net-(Q2-S)") (class "Default")
      (node (ref "C4") (pin "2") (pinfunction "2_2") (pintype "passive"))
      (node (ref "Q2") (pin "2") (pinfunction "S_2") (pintype "passive"))
      (node (ref "R4") (pin "2") (pinfunction "2_2") (pintype "passive"))
      (node (ref "R7") (pin "2") (pinfunction "2_2") (pintype "passive"))
      (node (ref "SV1") (pin "4") (pinfunction "4_4") (pintype "passive"))
      (node (ref "SV1") (pin "5") (pinfunction "5_5") (pintype "passive"))
      (node (ref "SV17") (pin "3") (pinfunction "3_3") (pintype "passive"))
    )
    (net (code "45") (name "Net-(R4-Pad1)") (class "Default")
      (node (ref "R4") (pin "1") (pinfunction "1_1") (pintype "passive"))
      (node (ref "SV16") (pin "3") (pinfunction "3_3") (pintype "passive"))
    )
    (net (code "46") (name "Net-(R11-CCW)") (class "Default")
      (node (ref "R11") (pin "1") (pinfunction "CCW_1") (pintype "passive"))
      (node (ref "SV26") (pin "18") (pinfunction "18_18") (pintype "passive"))
    )
    (net (code "47") (name "Net-(R11-WIPER)") (class "Default")
      (node (ref "R11") (pin "2") (pinfunction "WIPER_2") (pintype "passive"))
      (node (ref "SV26") (pin "5") (pinfunction "5_5") (pintype "passive"))
    )
    (net (code "48") (name "Net-(R18-Pad1)") (class "Default")
      (node (ref "R18") (pin "1") (pinfunction "1_1") (pintype "passive"))
      (node (ref "SV26") (pin "20") (pinfunction "20_20") (pintype "passive"))
    )
    (net (code "49") (name "Net-(R19-Pad2)") (class "Default")
      (node (ref "R19") (pin "2") (pinfunction "2_2") (pintype "passive"))
      (node (ref "SV29") (pin "2") (pinfunction "2_2") (pintype "passive"))
    )
    (net (code "50") (name "Net-(R20-Pad2)") (class "Default")
      (node (ref "R20") (pin "2") (pinfunction "2_2") (pintype "passive"))
      (node (ref "SV28") (pin "2") (pinfunction "2_2") (pintype "passive"))
    )
    (net (code "51") (name "Net-(R21-Pad2)") (class "Default")
      (node (ref "R21") (pin "2") (pinfunction "2_2") (pintype "passive"))
      (node (ref "SV27") (pin "2") (pinfunction "2_2") (pintype "passive"))
    )
    (net (code "52") (name "Net-(T1-B)") (class "Default")
      (node (ref "R6") (pin "1") (pinfunction "1_1") (pintype "passive"))
      (node (ref "T1") (pin "2") (pinfunction "B_2") (pintype "passive"))
    )
    (net (code "53") (name "Net-(T2-B)") (class "Default")
      (node (ref "R16") (pin "1") (pinfunction "1_1") (pintype "passive"))
      (node (ref "T2") (pin "2") (pinfunction "B_2") (pintype "passive"))
    )
    (net (code "54") (name "Net-(T2-C)") (class "Default")
      (node (ref "R18") (pin "2") (pinfunction "2_2") (pintype "passive"))
      (node (ref "T2") (pin "3") (pinfunction "C_3") (pintype "passive"))
    )
    (net (code "55") (name "Net-(T3-B)") (class "Default")
      (node (ref "R17") (pin "1") (pinfunction "1_1") (pintype "passive"))
      (node (ref "T3") (pin "2") (pinfunction "B_2") (pintype "passive"))
    )
    (net (code "56") (name "Net-(T3-C)") (class "Default")
      (node (ref "D2") (pin "A") (pinfunction "A_A") (pintype "passive"))
      (node (ref "SV30") (pin "2") (pinfunction "2_2") (pintype "passive"))
      (node (ref "T3") (pin "3") (pinfunction "C_3") (pintype "passive"))
    )
    (net (code "57") (name "Net-(T4-B)") (class "Default")
      (node (ref "R28") (pin "1") (pinfunction "1_1") (pintype "passive"))
      (node (ref "T4") (pin "2") (pinfunction "B_2") (pintype "passive"))
    )
    (net (code "58") (name "Net-(T4-E)") (class "Default")
      (node (ref "T4") (pin "1") (pinfunction "E_1") (pintype "passive"))
      (node (ref "U$1") (pin "7") (pinfunction "DAT0_DO_7") (pintype "bidirectional"))
    )
    (net (code "59") (name "Net-(U$1-CD_DAT3_CS)") (class "Default")
      (node (ref "R24") (pin "2") (pinfunction "2_2") (pintype "passive"))
      (node (ref "R27") (pin "1") (pinfunction "1_1") (pintype "passive"))
      (node (ref "U$1") (pin "2") (pinfunction "CD_DAT3_CS_2") (pintype "bidirectional"))
    )
    (net (code "60") (name "Net-(U$1-CLK)") (class "Default")
      (node (ref "R23") (pin "2") (pinfunction "2_2") (pintype "passive"))
      (node (ref "R25") (pin "1") (pinfunction "1_1") (pintype "passive"))
      (node (ref "U$1") (pin "5") (pinfunction "CLK_5") (pintype "bidirectional"))
    )
    (net (code "61") (name "Net-(U$1-CMD_DIN)") (class "Default")
      (node (ref "R22") (pin "1") (pinfunction "1_1") (pintype "passive"))
      (node (ref "R26") (pin "1") (pinfunction "1_1") (pintype "passive"))
      (node (ref "U$1") (pin "3") (pinfunction "CMD_DIN_3") (pintype "bidirectional"))
    )
    (net (code "62") (name "Net-(U4-XTAL1)") (class "Default")
      (node (ref "C2") (pin "2") (pinfunction "2_2") (pintype "passive"))
      (node (ref "Q1") (pin "1") (pinfunction "1_1") (pintype "passive"))
      (node (ref "U4") (pin "34") (pinfunction "XTAL1_34") (pintype "input"))
    )
    (net (code "63") (name "Net-(U4-XTAL2)") (class "Default")
      (node (ref "C1") (pin "2") (pinfunction "2_2") (pintype "passive"))
      (node (ref "Q1") (pin "2") (pinfunction "2_2") (pintype "passive"))
      (node (ref "U4") (pin "33") (pinfunction "XTAL2_33") (pintype "output"))
    )
    (net (code "64") (name "POW_LATCH") (class "Default")
      (node (ref "D1") (pin "A") (pinfunction "A_A") (pintype "passive"))
      (node (ref "U4") (pin "26") (pinfunction "(OC0A/OC1C/PCINT7)PB7_26") (pintype "bidirectional"))
    )
    (net (code "65") (name "POW_OFF") (class "Default")
      (node (ref "R5") (pin "1") (pinfunction "1_1") (pintype "passive"))
      (node (ref "SV16") (pin "1") (pinfunction "1_1") (pintype "passive"))
      (node (ref "U4") (pin "25") (pinfunction "(OC1B/PCINT6)PB6_25") (pintype "bidirectional"))
    )
    (net (code "66") (name "RESET") (class "Default")
      (node (ref "R8") (pin "1") (pinfunction "1_1") (pintype "passive"))
      (node (ref "SV15") (pin "5") (pinfunction "5_5") (pintype "passive"))
      (node (ref "SV27") (pin "1") (pinfunction "1_1") (pintype "passive"))
      (node (ref "U4") (pin "30") (pinfunction "RESET_30") (pintype "input"))
    )
    (net (code "67") (name "SCK") (class "Default")
      (node (ref "R23") (pin "1") (pinfunction "1_1") (pintype "passive"))
      (node (ref "SV15") (pin "3") (pinfunction "3_3") (pintype "passive"))
      (node (ref "U4") (pin "20") (pinfunction "(SCK/PCINT1)PB1_20") (pintype "bidirectional"))
    )
    (net (code "68") (name "SCL") (class "Default")
      (node (ref "R9") (pin "2") (pinfunction "2_2") (pintype "passive"))
      (node (ref "U1") (pin "6") (pinfunction "SCL_6") (pintype "bidirectional"))
      (node (ref "U4") (pin "43") (pinfunction "(SCL/INT0)PD0_43") (pintype "bidirectional"))
    )
    (net (code "69") (name "SDA") (class "Default")
      (node (ref "R10") (pin "2") (pinfunction "2_2") (pintype "passive"))
      (node (ref "U1") (pin "5") (pinfunction "SDA_5") (pintype "bidirectional"))
      (node (ref "U4") (pin "44") (pinfunction "(SDA/INT1)PD1_44") (pintype "bidirectional"))
    )
    (net (code "70") (name "SPKR") (class "Default")
      (node (ref "R13") (pin "2") (pinfunction "2_2") (pintype "passive"))
      (node (ref "U4") (pin "7") (pinfunction "(OC3C/INT5)PE5_7") (pintype "bidirectional"))
    )
    (net (code "71") (name "SS") (class "Default")
      (node (ref "R24") (pin "1") (pinfunction "1_1") (pintype "passive"))
      (node (ref "U4") (pin "19") (pinfunction "(SS/PCINT0)PB0_19") (pintype "bidirectional"))
    )
    (net (code "72") (name "SWA_DN") (class "Default")
      (node (ref "SV2") (pin "1") (pinfunction "1_1") (pintype "passive"))
      (node (ref "U4") (pin "54") (pinfunction "(A9)PC1_54") (pintype "bidirectional"))
    )
    (net (code "73") (name "SWA_UP") (class "Default")
      (node (ref "SV2") (pin "3") (pinfunction "3_3") (pintype "passive"))
      (node (ref "U4") (pin "53") (pinfunction "(A8)PC0_53") (pintype "bidirectional"))
    )
    (net (code "74") (name "SWB_DN") (class "Default")
      (node (ref "SV3") (pin "1") (pinfunction "1_1") (pintype "passive"))
      (node (ref "U4") (pin "56") (pinfunction "(A11)PC3_56") (pintype "bidirectional"))
    )
    (net (code "75") (name "SWB_UP") (class "Default")
      (node (ref "SV3") (pin "3") (pinfunction "3_3") (pintype "passive"))
      (node (ref "U4") (pin "55") (pinfunction "(A10)PC2_55") (pintype "bidirectional"))
    )
    (net (code "76") (name "SWC_DN") (class "Default")
      (node (ref "SV4") (pin "1") (pinfunction "1_1") (pintype "passive"))
      (node (ref "U4") (pin "58") (pinfunction "(A13)PC5_58") (pintype "bidirectional"))
    )
    (net (code "77") (name "SWC_UP") (class "Default")
      (node (ref "SV4") (pin "3") (pinfunction "3_3") (pintype "passive"))
      (node (ref "U4") (pin "57") (pinfunction "(A12)PC4_57") (pintype "bidirectional"))
    )
    (net (code "78") (name "SWD_DN") (class "Default")
      (node (ref "SV5") (pin "1") (pinfunction "1_1") (pintype "passive"))
      (node (ref "U4") (pin "60") (pinfunction "(A15)PC7_60") (pintype "bidirectional"))
    )
    (net (code "79") (name "SWD_UP") (class "Default")
      (node (ref "SV5") (pin "3") (pinfunction "3_3") (pintype "passive"))
      (node (ref "U4") (pin "59") (pinfunction "(A14)PC6_59") (pintype "bidirectional"))
    )
    (net (code "80") (name "SWE_DN") (class "Default")
      (node (ref "SV6") (pin "1") (pinfunction "1_1") (pintype "passive"))
      (node (ref "U4") (pin "24") (pinfunction "(OC1A/PCINT5)PB5_24") (pintype "bidirectional"))
    )
    (net (code "81") (name "SWE_UP") (class "Default")
      (node (ref "SV6") (pin "3") (pinfunction "3_3") (pintype "passive"))
      (node (ref "U4") (pin "23") (pinfunction "(OC2A/PCINT4)PB4_23") (pintype "bidirectional"))
    )
    (net (code "82") (name "SWF_DN") (class "Default")
      (node (ref "SV7") (pin "1") (pinfunction "1_1") (pintype "passive"))
      (node (ref "U4") (pin "52") (pinfunction "(RD)PG1_52") (pintype "bidirectional"))
    )
    (net (code "83") (name "SWF_UP") (class "Default")
      (node (ref "SV7") (pin "3") (pinfunction "3_3") (pintype "passive"))
      (node (ref "U4") (pin "51") (pinfunction "(WR)PG0_51") (pintype "bidirectional"))
    )
    (net (code "84") (name "SWG_DN") (class "Default")
      (node (ref "SV8") (pin "1") (pinfunction "1_1") (pintype "passive"))
      (node (ref "U4") (pin "82") (pinfunction "PK7(ADC15/PCINT23)_82") (pintype "bidirectional"))
    )
    (net (code "85") (name "SWG_UP") (class "Default")
      (node (ref "SV8") (pin "3") (pinfunction "3_3") (pintype "passive"))
      (node (ref "U4") (pin "90") (pinfunction "(ADC7/TDI)PF7_90") (pintype "bidirectional"))
    )
    (net (code "86") (name "SWH_DN") (class "Default")
      (node (ref "SV9") (pin "1") (pinfunction "1_1") (pintype "passive"))
      (node (ref "U4") (pin "50") (pinfunction "(T0)PD7_50") (pintype "bidirectional"))
    )
    (net (code "87") (name "SWH_UP") (class "Default")
      (node (ref "SV9") (pin "3") (pinfunction "3_3") (pintype "passive"))
      (node (ref "U4") (pin "5") (pinfunction "(OC3A/AIN1)PE3_5") (pintype "bidirectional"))
    )
    (net (code "88") (name "TRIM_X1_DN") (class "Default")
      (node (ref "SV13") (pin "1") (pinfunction "1_1") (pintype "passive"))
      (node (ref "U4") (pin "35") (pinfunction "PL0(ICP4)_35") (pintype "bidirectional"))
    )
    (net (code "89") (name "TRIM_X1_UP") (class "Default")
      (node (ref "SV13") (pin "3") (pinfunction "3_3") (pintype "passive"))
      (node (ref "U4") (pin "36") (pinfunction "PL1(ICP5)_36") (pintype "bidirectional"))
    )
    (net (code "90") (name "TRIM_X2_DN") (class "Default")
      (node (ref "SV10") (pin "1") (pinfunction "1_1") (pintype "passive"))
      (node (ref "U4") (pin "41") (pinfunction "PL6_41") (pintype "bidirectional"))
    )
    (net (code "91") (name "TRIM_X2_UP") (class "Default")
      (node (ref "SV10") (pin "3") (pinfunction "3_3") (pintype "passive"))
      (node (ref "U4") (pin "42") (pinfunction "PL7_42") (pintype "bidirectional"))
    )
    (net (code "92") (name "TRIM_Y1_DN") (class "Default")
      (node (ref "SV12") (pin "1") (pinfunction "1_1") (pintype "passive"))
      (node (ref "U4") (pin "37") (pinfunction "PL2(T5)_37") (pintype "bidirectional"))
    )
    (net (code "93") (name "TRIM_Y1_UP") (class "Default")
      (node (ref "SV12") (pin "3") (pinfunction "3_3") (pintype "passive"))
      (node (ref "U4") (pin "38") (pinfunction "PL3(OC5A)_38") (pintype "bidirectional"))
    )
    (net (code "94") (name "TRIM_Y2_DN") (class "Default")
      (node (ref "SV11") (pin "1") (pinfunction "1_1") (pintype "passive"))
      (node (ref "U4") (pin "39") (pinfunction "PL4(OC5B)_39") (pintype "bidirectional"))
    )
    (net (code "95") (name "TRIM_Y2_UP") (class "Default")
      (node (ref "SV11") (pin "3") (pinfunction "3_3") (pintype "passive"))
      (node (ref "U4") (pin "40") (pinfunction "PL5(OC5C)_40") (pintype "bidirectional"))
    )
    (net (code "96") (name "X1_AXIS") (class "Default")
      (node (ref "C16") (pin "2") (pinfunction "2_2") (pintype "passive"))
      (node (ref "SV23") (pin "2") (pinfunction "2_2") (pintype "passive"))
      (node (ref "U4") (pin "94") (pinfunction "(ADC3)PF3_94") (pintype "bidirectional"))
    )
    (net (code "97") (name "X2_AXIS") (class "Default")
      (node (ref "C13") (pin "2") (pinfunction "2_2") (pintype "passive"))
      (node (ref "SV20") (pin "2") (pinfunction "2_2") (pintype "passive"))
      (node (ref "U4") (pin "97") (pinfunction "(ADC0)PF0_97") (pintype "bidirectional"))
    )
    (net (code "98") (name "X3_AXIS") (class "Default")
      (node (ref "C20") (pin "2") (pinfunction "2_2") (pintype "passive"))
      (node (ref "SV31") (pin "2") (pinfunction "2_2") (pintype "passive"))
      (node (ref "U4") (pin "86") (pinfunction "PK3(ADC11/PCINT19)_86") (pintype "bidirectional"))
    )
    (net (code "99") (name "X4_AXIS") (class "Default")
      (node (ref "C22") (pin "2") (pinfunction "2_2") (pintype "passive"))
      (node (ref "SV33") (pin "2") (pinfunction "2_2") (pintype "passive"))
      (node (ref "U4") (pin "84") (pinfunction "PK5(ADC13/PCINT21)_84") (pintype "bidirectional"))
    )
    (net (code "100") (name "Y1_AXIS") (class "Default")
      (node (ref "C15") (pin "2") (pinfunction "2_2") (pintype "passive"))
      (node (ref "SV22") (pin "2") (pinfunction "2_2") (pintype "passive"))
      (node (ref "U4") (pin "95") (pinfunction "(ADC2)PF2_95") (pintype "bidirectional"))
    )
    (net (code "101") (name "Y2_AXIS") (class "Default")
      (node (ref "C14") (pin "2") (pinfunction "2_2") (pintype "passive"))
      (node (ref "SV21") (pin "2") (pinfunction "2_2") (pintype "passive"))
      (node (ref "U4") (pin "96") (pinfunction "(ADC1)PF1_96") (pintype "bidirectional"))
    )
    (net (code "102") (name "Y3_AXIS") (class "Default")
      (node (ref "C21") (pin "2") (pinfunction "2_2") (pintype "passive"))
      (node (ref "SV32") (pin "2") (pinfunction "2_2") (pintype "passive"))
      (node (ref "U4") (pin "87") (pinfunction "PK2(ADC10/PCINT18)_87") (pintype "bidirectional"))
    )
    (net (code "103") (name "Y4_AXIS") (class "Default")
      (node (ref "C23") (pin "2") (pinfunction "2_2") (pintype "passive"))
      (node (ref "SV34") (pin "2") (pinfunction "2_2") (pintype "passive"))
      (node (ref "U4") (pin "85") (pinfunction "PK4(ADC12/PCINT20)_85") (pintype "bidirectional"))
    )
    (net (code "104") (name "Z1_AXIS") (class "Default")
      (node (ref "C8") (pin "1") (pinfunction "1_1") (pintype "passive"))
      (node (ref "SV19") (pin "2") (pinfunction "2_2") (pintype "passive"))
      (node (ref "U4") (pin "88") (pinfunction "PK1(ADC9/PCINT17)_88") (pintype "bidirectional"))
    )
    (net (code "105") (name "Z2_AXIS") (class "Default")
      (node (ref "C9") (pin "2") (pinfunction "2_2") (pintype "passive"))
      (node (ref "SV18") (pin "2") (pinfunction "2_2") (pintype "passive"))
      (node (ref "U4") (pin "89") (pinfunction "PK0(ADC8/PCINT16)_89") (pintype "bidirectional"))
    )
    (net (code "106") (name "unconnected-(SV14-Pad2)") (class "Default")
      (node (ref "SV14") (pin "2") (pinfunction "2_2") (pintype "passive"))
    )
    (net (code "107") (name "unconnected-(SV15-Pad2)") (class "Default")
      (node (ref "SV15") (pin "2") (pinfunction "2_2") (pintype "passive"))
    )
    (net (code "108") (name "unconnected-(SV28-Pad1)") (class "Default")
      (node (ref "SV28") (pin "1") (pinfunction "1_1") (pintype "passive"))
    )
    (net (code "109") (name "unconnected-(SV29-Pad1)") (class "Default")
      (node (ref "SV29") (pin "1") (pinfunction "1_1") (pintype "passive"))
    )
    (net (code "110") (name "unconnected-(SV30-Pad3)") (class "Default")
      (node (ref "SV30") (pin "3") (pinfunction "3_3") (pintype "passive"))
    )
    (net (code "111") (name "unconnected-(U$1-DAT1-Pad8)") (class "Default")
      (node (ref "U$1") (pin "8") (pinfunction "DAT1_8") (pintype "bidirectional"))
    )
    (net (code "112") (name "unconnected-(U$1-DAT2-Pad1)") (class "Default")
      (node (ref "U$1") (pin "1") (pinfunction "DAT2_1") (pintype "bidirectional"))
    )
    (net (code "113") (name "unconnected-(U$1-PadCD)") (class "Default")
      (node (ref "U$1") (pin "CD") (pinfunction "CD_CD") (pintype "bidirectional"))
    )
    (net (code "114") (name "unconnected-(U4-(CLKO{slash}ICP3{slash}INT7)PE7-Pad9)") (class "Default")
      (node (ref "U4") (pin "9") (pinfunction "(CLKO/ICP3/INT7)PE7_9") (pintype "bidirectional"))
    )
    (net (code "115") (name "unconnected-(U4-(ICP1)PD4-Pad47)") (class "Default")
      (node (ref "U4") (pin "47") (pinfunction "(ICP1)PD4_47") (pintype "bidirectional"))
    )
    (net (code "116") (name "unconnected-(U4-(T1)PD6-Pad49)") (class "Default")
      (node (ref "U4") (pin "49") (pinfunction "(T1)PD6_49") (pintype "bidirectional"))
    )
    (net (code "117") (name "unconnected-(U4-(T3{slash}INT6)PE6-Pad8)") (class "Default")
      (node (ref "U4") (pin "8") (pinfunction "(T3/INT6)PE6_8") (pintype "bidirectional"))
    )
    (net (code "118") (name "unconnected-(U4-(TOSC1)PG4-Pad29)") (class "Default")
      (node (ref "U4") (pin "29") (pinfunction "(TOSC1)PG4_29") (pintype "bidirectional"))
    )
    (net (code "119") (name "unconnected-(U4-(TOSC2)PG3-Pad28)") (class "Default")
      (node (ref "U4") (pin "28") (pinfunction "(TOSC2)PG3_28") (pintype "bidirectional"))
    )
    (net (code "120") (name "unconnected-(U4-(XCK0{slash}AIN0)PE2-Pad4)") (class "Default")
      (node (ref "U4") (pin "4") (pinfunction "(XCK0/AIN0)PE2_4") (pintype "bidirectional"))
    )
    (net (code "121") (name "unconnected-(U4-(XCK1)PD5-Pad48)") (class "Default")
      (node (ref "U4") (pin "48") (pinfunction "(XCK1)PD5_48") (pintype "bidirectional"))
    )
    (net (code "122") (name "unconnected-(U4-AREF-Pad98)") (class "Default")
      (node (ref "U4") (pin "98") (pinfunction "AREF_98") (pintype "bidirectional"))
    )
    (net (code "123") (name "unconnected-(U4-PH2(XCK2)-Pad14)") (class "Default")
      (node (ref "U4") (pin "14") (pinfunction "PH2(XCK2)_14") (pintype "bidirectional"))
    )
    (net (code "124") (name "unconnected-(U4-PH7(T4)-Pad27)") (class "Default")
      (node (ref "U4") (pin "27") (pinfunction "PH7(T4)_27") (pintype "bidirectional"))
    )
    (net (code "125") (name "unconnected-(U4-PJ2(XCK3{slash}PCINT11)-Pad65)") (class "Default")
      (node (ref "U4") (pin "65") (pinfunction "PJ2(XCK3/PCINT11)_65") (pintype "bidirectional"))
    )
    (net (code "126") (name "unconnected-(U4-PJ3(PCINT12)-Pad66)") (class "Default")
      (node (ref "U4") (pin "66") (pinfunction "PJ3(PCINT12)_66") (pintype "bidirectional"))
    )
    (net (code "127") (name "unconnected-(U4-PJ4(PCINT13)-Pad67)") (class "Default")
      (node (ref "U4") (pin "67") (pinfunction "PJ4(PCINT13)_67") (pintype "bidirectional"))
    )
    (net (code "128") (name "unconnected-(U4-PJ5(PCINT14)-Pad68)") (class "Default")
      (node (ref "U4") (pin "68") (pinfunction "PJ5(PCINT14)_68") (pintype "bidirectional"))
    )
    (net (code "129") (name "unconnected-(U4-PJ6(PCINT15)-Pad69)") (class "Default")
      (node (ref "U4") (pin "69") (pinfunction "PJ6(PCINT15)_69") (pintype "bidirectional"))
    )
    (net (code "130") (name "unconnected-(U4-PJ7-Pad79)") (class "Default")
      (node (ref "U4") (pin "79") (pinfunction "PJ7_79") (pintype "bidirectional"))
    )
  )
)
